# shiftLight.net
KiCad netlist of a schematic drawn in EAGLE
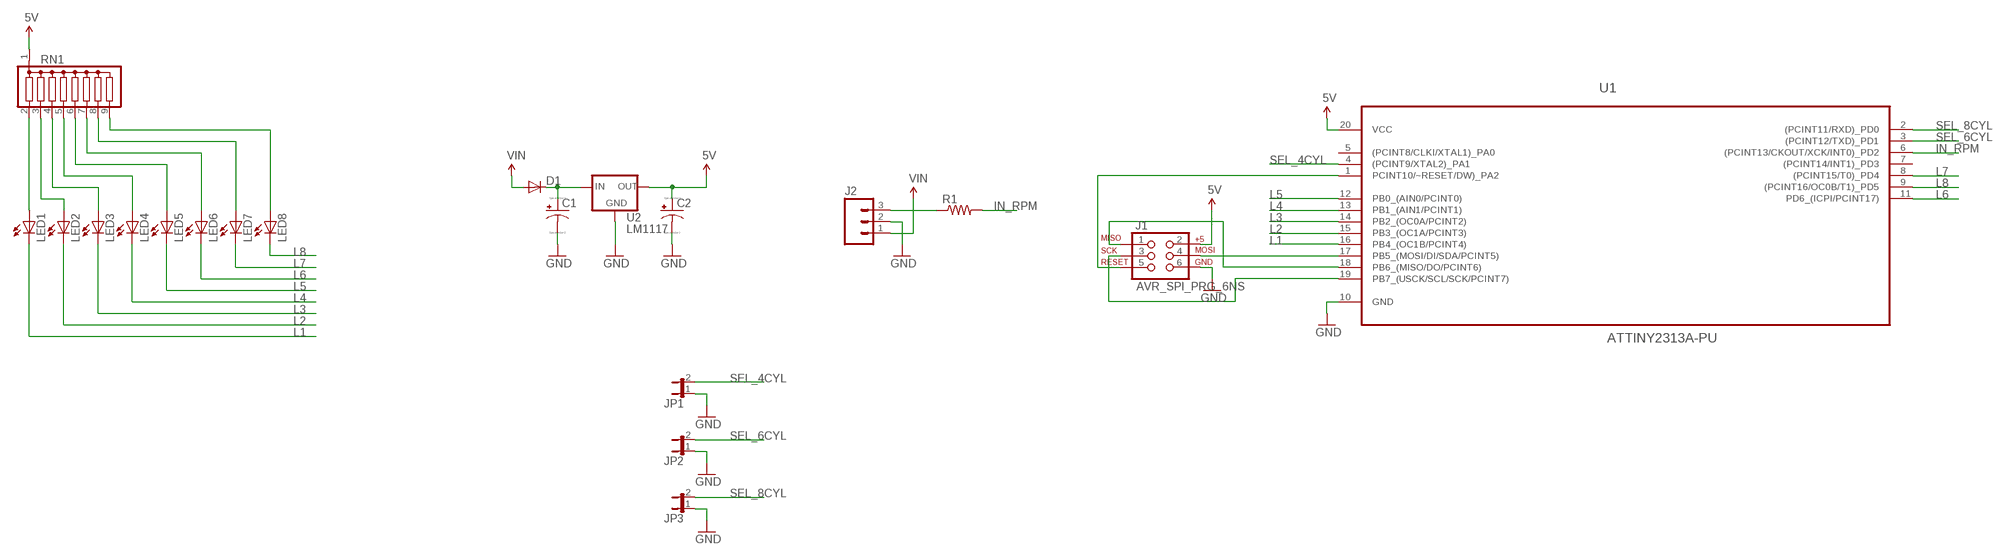
[diagram p0: schematic, sheet 1]

(export (version "E")
  (design (tool "Eeschema 10.0.6"))
  (components
    (comp (ref "C1")
      (value "CPOL-USE3.5-8")
      (footprint "eagle-import:E3,5-8")
      (libsource (lib "eagle-import") (part "CPOL-USE3.5-8"))
    )
    (comp (ref "C2")
      (value "CPOL-USE3.5-8")
      (footprint "eagle-import:E3,5-8")
      (libsource (lib "eagle-import") (part "CPOL-USE3.5-8"))
    )
    (comp (ref "D1")
      (value "DIODEPTH")
      (footprint "eagle-import:DIODE-1N4001")
      (libsource (lib "eagle-import") (part "DIODEPTH"))
    )
    (comp (ref "J1")
      (value "AVR_SPI_PRG_6NS")
      (footprint "eagle-import:2X3-NS")
      (libsource (lib "eagle-import") (part "AVR_SPI_PRG_6NS"))
    )
    (comp (ref "J2")
      (value "M03SCREW")
      (footprint "eagle-import:SCREWTERMINAL-3.5MM-3")
      (libsource (lib "eagle-import") (part "M03SCREW"))
    )
    (comp (ref "JP1")
      (value "JUMPER-2SMD-NO")
      (footprint "eagle-import:SJ_2S-NO")
      (libsource (lib "eagle-import") (part "JUMPER-2SMD-NO"))
    )
    (comp (ref "JP2")
      (value "JUMPER-2SMD-NO")
      (footprint "eagle-import:SJ_2S-NO")
      (libsource (lib "eagle-import") (part "JUMPER-2SMD-NO"))
    )
    (comp (ref "JP3")
      (value "JUMPER-2SMD-NO")
      (footprint "eagle-import:SJ_2S-NO")
      (libsource (lib "eagle-import") (part "JUMPER-2SMD-NO"))
    )
    (comp (ref "LED1")
      (value "LED5MM")
      (footprint "eagle-import:LED5MM")
      (libsource (lib "eagle-import") (part "LED5MM"))
    )
    (comp (ref "LED2")
      (value "LED5MM")
      (footprint "eagle-import:LED5MM")
      (libsource (lib "eagle-import") (part "LED5MM"))
    )
    (comp (ref "LED3")
      (value "LED5MM")
      (footprint "eagle-import:LED5MM")
      (libsource (lib "eagle-import") (part "LED5MM"))
    )
    (comp (ref "LED4")
      (value "LED5MM")
      (footprint "eagle-import:LED5MM")
      (libsource (lib "eagle-import") (part "LED5MM"))
    )
    (comp (ref "LED5")
      (value "LED5MM")
      (footprint "eagle-import:LED5MM")
      (libsource (lib "eagle-import") (part "LED5MM"))
    )
    (comp (ref "LED6")
      (value "LED5MM")
      (footprint "eagle-import:LED5MM")
      (libsource (lib "eagle-import") (part "LED5MM"))
    )
    (comp (ref "LED7")
      (value "LED5MM")
      (footprint "eagle-import:LED5MM")
      (libsource (lib "eagle-import") (part "LED5MM"))
    )
    (comp (ref "LED8")
      (value "LED5MM")
      (footprint "eagle-import:LED5MM")
      (libsource (lib "eagle-import") (part "LED5MM"))
    )
    (comp (ref "R1")
      (value "RESISTORPTH-1/4W")
      (footprint "eagle-import:AXIAL-0.4")
      (libsource (lib "eagle-import") (part "RESISTORPTH-1/4W"))
    )
    (comp (ref "RN1")
      (value "G08R")
      (footprint "eagle-import:SIL9")
      (libsource (lib "eagle-import") (part "G08R"))
    )
    (comp (ref "U1")
      (value "ATTINY2313A-PU")
      (footprint "eagle-import:DIP254P762X533-20")
      (libsource (lib "eagle-import") (part "ATTINY2313A-PU"))
    )
    (comp (ref "U2")
      (value "LM1117")
      (footprint "eagle-import:TO-220-ALT")
      (libsource (lib "eagle-import") (part "V_REG_78XX-TO-220"))
    )
  )
  (nets
    (net (code "1") (name "/IN_RPM") (class "Default")
      (node (ref "R1") (pin "P$2") (pinfunction "2_P$2") (pintype "passive"))
      (node (ref "U1") (pin "6") (pinfunction "(PCINT13/CKOUT/XCK/INT0)_PD2_6") (pintype "bidirectional"))
    )
    (net (code "2") (name "/L1") (class "Default")
      (node (ref "LED1") (pin "K") (pinfunction "C_K") (pintype "passive"))
      (node (ref "U1") (pin "16") (pinfunction "PB4_(OC1B/PCINT4)_16") (pintype "bidirectional"))
    )
    (net (code "3") (name "/L2") (class "Default")
      (node (ref "LED2") (pin "K") (pinfunction "C_K") (pintype "passive"))
      (node (ref "U1") (pin "15") (pinfunction "PB3_(OC1A/PCINT3)_15") (pintype "bidirectional"))
    )
    (net (code "4") (name "/L3") (class "Default")
      (node (ref "LED3") (pin "K") (pinfunction "C_K") (pintype "passive"))
      (node (ref "U1") (pin "14") (pinfunction "PB2_(OC0A/PCINT2)_14") (pintype "bidirectional"))
    )
    (net (code "5") (name "/L4") (class "Default")
      (node (ref "LED4") (pin "K") (pinfunction "C_K") (pintype "passive"))
      (node (ref "U1") (pin "13") (pinfunction "PB1_(AIN1/PCINT1)_13") (pintype "bidirectional"))
    )
    (net (code "6") (name "/L5") (class "Default")
      (node (ref "LED5") (pin "K") (pinfunction "C_K") (pintype "passive"))
      (node (ref "U1") (pin "12") (pinfunction "PB0_(AIN0/PCINT0)_12") (pintype "bidirectional"))
    )
    (net (code "7") (name "/L6") (class "Default")
      (node (ref "LED6") (pin "K") (pinfunction "C_K") (pintype "passive"))
      (node (ref "U1") (pin "11") (pinfunction "PD6_(ICPI/PCINT17)_11") (pintype "bidirectional"))
    )
    (net (code "8") (name "/L7") (class "Default")
      (node (ref "LED7") (pin "K") (pinfunction "C_K") (pintype "passive"))
      (node (ref "U1") (pin "8") (pinfunction "(PCINT15/T0)_PD4_8") (pintype "bidirectional"))
    )
    (net (code "9") (name "/L8") (class "Default")
      (node (ref "LED8") (pin "K") (pinfunction "C_K") (pintype "passive"))
      (node (ref "U1") (pin "9") (pinfunction "(PCINT16/OC0B/T1)_PD5_9") (pintype "bidirectional"))
    )
    (net (code "10") (name "/SEL_4CYL") (class "Default")
      (node (ref "JP1") (pin "2") (pinfunction "2_2") (pintype "passive"))
      (node (ref "U1") (pin "4") (pinfunction "(PCINT9/XTAL2)_PA1_4") (pintype "bidirectional"))
    )
    (net (code "11") (name "/SEL_6CYL") (class "Default")
      (node (ref "JP2") (pin "2") (pinfunction "2_2") (pintype "passive"))
      (node (ref "U1") (pin "3") (pinfunction "(PCINT12/TXD)_PD1_3") (pintype "bidirectional"))
    )
    (net (code "12") (name "/SEL_8CYL") (class "Default")
      (node (ref "JP3") (pin "2") (pinfunction "2_2") (pintype "passive"))
      (node (ref "U1") (pin "2") (pinfunction "(PCINT11/RXD)_PD0_2") (pintype "bidirectional"))
    )
    (net (code "13") (name "5V") (class "Default")
      (node (ref "C2") (pin "+") (pinfunction "+_+") (pintype "passive"))
      (node (ref "J1") (pin "2") (pinfunction "2_2") (pintype "passive"))
      (node (ref "RN1") (pin "1") (pinfunction "1_1") (pintype "passive"))
      (node (ref "U1") (pin "20") (pinfunction "VCC_20") (pintype "power_in"))
      (node (ref "U2") (pin "OUT") (pinfunction "OUT_OUT") (pintype "output"))
    )
    (net (code "14") (name "GND") (class "Default")
      (node (ref "C1") (pin "-") (pinfunction "-_-") (pintype "passive"))
      (node (ref "C2") (pin "-") (pinfunction "-_-") (pintype "passive"))
      (node (ref "J1") (pin "6") (pinfunction "6_6") (pintype "passive"))
      (node (ref "J2") (pin "2") (pinfunction "2_2") (pintype "passive"))
      (node (ref "JP1") (pin "1") (pinfunction "1_1") (pintype "passive"))
      (node (ref "JP2") (pin "1") (pinfunction "1_1") (pintype "passive"))
      (node (ref "JP3") (pin "1") (pinfunction "1_1") (pintype "passive"))
      (node (ref "U1") (pin "10") (pinfunction "GND_10") (pintype "passive"))
      (node (ref "U2") (pin "GND") (pinfunction "GND_GND") (pintype "input"))
    )
    (net (code "15") (name "Net-(C1-Pad+)") (class "Default")
      (node (ref "C1") (pin "+") (pinfunction "+_+") (pintype "passive"))
      (node (ref "D1") (pin "C") (pinfunction "C_C") (pintype "passive"))
      (node (ref "U2") (pin "IN") (pinfunction "IN_IN") (pintype "input"))
    )
    (net (code "16") (name "Net-(LED1-PadA)") (class "Default")
      (node (ref "LED1") (pin "A") (pinfunction "A_A") (pintype "passive"))
      (node (ref "RN1") (pin "2") (pinfunction "2_2") (pintype "passive"))
    )
    (net (code "17") (name "Net-(LED2-PadA)") (class "Default")
      (node (ref "LED2") (pin "A") (pinfunction "A_A") (pintype "passive"))
      (node (ref "RN1") (pin "3") (pinfunction "3_3") (pintype "passive"))
    )
    (net (code "18") (name "Net-(LED3-PadA)") (class "Default")
      (node (ref "LED3") (pin "A") (pinfunction "A_A") (pintype "passive"))
      (node (ref "RN1") (pin "4") (pinfunction "4_4") (pintype "passive"))
    )
    (net (code "19") (name "Net-(LED4-PadA)") (class "Default")
      (node (ref "LED4") (pin "A") (pinfunction "A_A") (pintype "passive"))
      (node (ref "RN1") (pin "5") (pinfunction "5_5") (pintype "passive"))
    )
    (net (code "20") (name "Net-(LED5-PadA)") (class "Default")
      (node (ref "LED5") (pin "A") (pinfunction "A_A") (pintype "passive"))
      (node (ref "RN1") (pin "6") (pinfunction "6_6") (pintype "passive"))
    )
    (net (code "21") (name "Net-(LED6-PadA)") (class "Default")
      (node (ref "LED6") (pin "A") (pinfunction "A_A") (pintype "passive"))
      (node (ref "RN1") (pin "7") (pinfunction "7_7") (pintype "passive"))
    )
    (net (code "22") (name "Net-(LED7-PadA)") (class "Default")
      (node (ref "LED7") (pin "A") (pinfunction "A_A") (pintype "passive"))
      (node (ref "RN1") (pin "8") (pinfunction "8_8") (pintype "passive"))
    )
    (net (code "23") (name "Net-(LED8-PadA)") (class "Default")
      (node (ref "LED8") (pin "A") (pinfunction "A_A") (pintype "passive"))
      (node (ref "RN1") (pin "9") (pinfunction "9_9") (pintype "passive"))
    )
    (net (code "24") (name "Net-(R1-1)") (class "Default")
      (node (ref "J2") (pin "3") (pinfunction "3_3") (pintype "passive"))
      (node (ref "R1") (pin "P$1") (pinfunction "1_P$1") (pintype "passive"))
    )
    (net (code "25") (name "Net-(U1-PB5_(MOSI{slash}DI{slash}SDA{slash}PCINT5))") (class "Default")
      (node (ref "J1") (pin "4") (pinfunction "4_4") (pintype "passive"))
      (node (ref "U1") (pin "17") (pinfunction "PB5_(MOSI/DI/SDA/PCINT5)_17") (pintype "bidirectional"))
    )
    (net (code "26") (name "Net-(U1-PB6_(MISO{slash}DO{slash}PCINT6))") (class "Default")
      (node (ref "J1") (pin "1") (pinfunction "1_1") (pintype "passive"))
      (node (ref "U1") (pin "18") (pinfunction "PB6_(MISO/DO/PCINT6)_18") (pintype "bidirectional"))
    )
    (net (code "27") (name "Net-(U1-PB7_(USCK{slash}SCL{slash}SCK{slash}PCINT7))") (class "Default")
      (node (ref "J1") (pin "3") (pinfunction "3_3") (pintype "passive"))
      (node (ref "U1") (pin "19") (pinfunction "PB7_(USCK/SCL/SCK/PCINT7)_19") (pintype "bidirectional"))
    )
    (net (code "28") (name "Net-(U1-PCINT10{slash}~{RESET{slash}DW})_PA2)") (class "Default")
      (node (ref "J1") (pin "5") (pinfunction "5_5") (pintype "passive"))
      (node (ref "U1") (pin "1") (pinfunction "PCINT10/~{RESET/DW})_PA2_1") (pintype "bidirectional"))
    )
    (net (code "29") (name "VIN") (class "Default")
      (node (ref "D1") (pin "A") (pinfunction "A_A") (pintype "passive"))
      (node (ref "J2") (pin "1") (pinfunction "1_1") (pintype "passive"))
    )
    (net (code "30") (name "unconnected-(U1-(PCINT8{slash}CLKI{slash}XTAL1)_PA0-Pad5)") (class "Default")
      (node (ref "U1") (pin "5") (pinfunction "(PCINT8/CLKI/XTAL1)_PA0_5") (pintype "bidirectional"))
    )
    (net (code "31") (name "unconnected-(U1-(PCINT14{slash}INT1)_PD3-Pad7)") (class "Default")
      (node (ref "U1") (pin "7") (pinfunction "(PCINT14/INT1)_PD3_7") (pintype "bidirectional"))
    )
  )
)
